# ledterne_driver.net
KiCad netlist of a schematic drawn in EAGLE
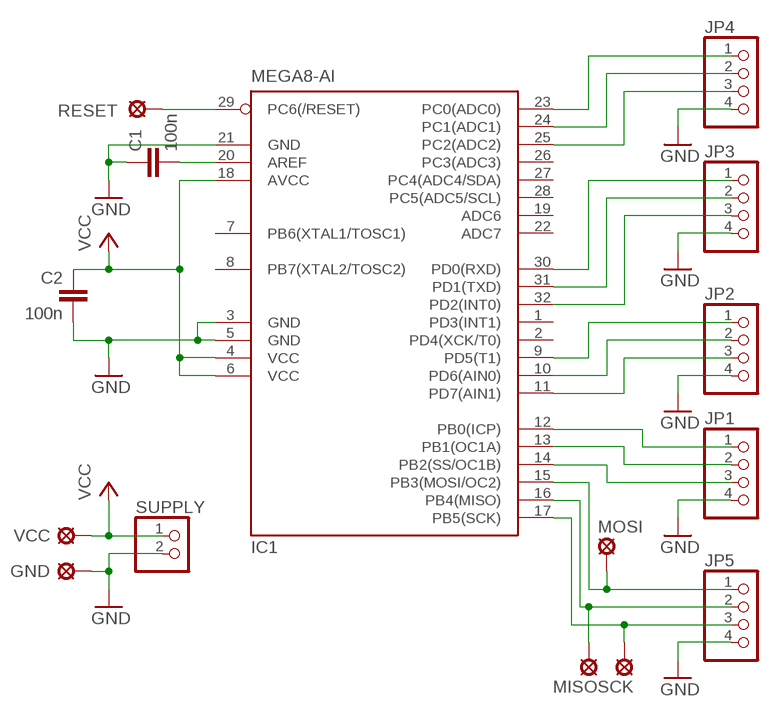
[diagram p0: schematic, sheet 1]

(export (version "E")
  (design (tool "Eeschema 10.0.6"))
  (components
    (comp (ref "C1")
      (value "100n")
      (footprint "eagle-import:C0805K")
      (libsource (lib "eagle-import") (part "C-EUC0805K"))
    )
    (comp (ref "C2")
      (value "100n")
      (footprint "eagle-import:C0805K")
      (libsource (lib "eagle-import") (part "C-EUC0805K"))
    )
    (comp (ref "GND")
      (value "LSP10")
      (footprint "eagle-import:LSP10")
      (libsource (lib "eagle-import") (part "LSP10"))
    )
    (comp (ref "IC1")
      (value "MEGA8-AI")
      (footprint "eagle-import:TQFP32-08")
      (fields (field (name "MPN") "ATMEGA8-16AU"))
      (libsource (lib "eagle-import") (part "MEGA8-AI"))
    )
    (comp (ref "JP1")
      (value "PINHD-1X4/90")
      (footprint "eagle-import:1X04_90")
      (libsource (lib "eagle-import") (part "PINHD-1X4/90"))
    )
    (comp (ref "JP2")
      (value "PINHD-1X4/90")
      (footprint "eagle-import:1X04_90")
      (libsource (lib "eagle-import") (part "PINHD-1X4/90"))
    )
    (comp (ref "JP3")
      (value "PINHD-1X4/90")
      (footprint "eagle-import:1X04_90")
      (libsource (lib "eagle-import") (part "PINHD-1X4/90"))
    )
    (comp (ref "JP4")
      (value "PINHD-1X4/90")
      (footprint "eagle-import:1X04_90")
      (libsource (lib "eagle-import") (part "PINHD-1X4/90"))
    )
    (comp (ref "JP5")
      (value "PINHD-1X4/90")
      (footprint "eagle-import:1X04_90")
      (libsource (lib "eagle-import") (part "PINHD-1X4/90"))
    )
    (comp (ref "MISO")
      (value "LSP10")
      (footprint "eagle-import:LSP10")
      (libsource (lib "eagle-import") (part "LSP10"))
    )
    (comp (ref "MOSI")
      (value "LSP10")
      (footprint "eagle-import:LSP10")
      (libsource (lib "eagle-import") (part "LSP10"))
    )
    (comp (ref "RESET")
      (value "LSP10")
      (footprint "eagle-import:LSP10")
      (libsource (lib "eagle-import") (part "LSP10"))
    )
    (comp (ref "SCK")
      (value "LSP10")
      (footprint "eagle-import:LSP10")
      (libsource (lib "eagle-import") (part "LSP10"))
    )
    (comp (ref "SUPPLY")
      (value "PINHD-1X2")
      (footprint "eagle-import:1X02")
      (libsource (lib "eagle-import") (part "PINHD-1X2"))
    )
    (comp (ref "VCC")
      (value "LSP10")
      (footprint "eagle-import:LSP10")
      (libsource (lib "eagle-import") (part "LSP10"))
    )
  )
  (nets
    (net (code "1") (name "GND") (class "Default")
      (node (ref "C1") (pin "1") (pinfunction "1_1") (pintype "passive"))
      (node (ref "C2") (pin "2") (pinfunction "2_2") (pintype "passive"))
      (node (ref "GND") (pin "MP") (pinfunction "MP_MP") (pintype "passive"))
      (node (ref "IC1") (pin "21") (pinfunction "GND_21") (pintype "power_in"))
      (node (ref "IC1") (pin "3") (pinfunction "GND_3") (pintype "power_in"))
      (node (ref "IC1") (pin "5") (pinfunction "GND_5") (pintype "power_in"))
      (node (ref "JP1") (pin "4") (pinfunction "4_4") (pintype "passive"))
      (node (ref "JP2") (pin "4") (pinfunction "4_4") (pintype "passive"))
      (node (ref "JP3") (pin "4") (pinfunction "4_4") (pintype "passive"))
      (node (ref "JP4") (pin "4") (pinfunction "4_4") (pintype "passive"))
      (node (ref "JP5") (pin "4") (pinfunction "4_4") (pintype "passive"))
      (node (ref "SUPPLY") (pin "2") (pinfunction "2_2") (pintype "passive"))
    )
    (net (code "2") (name "Net-(IC1-AREF)") (class "Default")
      (node (ref "C1") (pin "2") (pinfunction "2_2") (pintype "passive"))
      (node (ref "IC1") (pin "20") (pinfunction "AREF_20") (pintype "passive"))
    )
    (net (code "3") (name "Net-(IC1-PB0(ICP))") (class "Default")
      (node (ref "IC1") (pin "12") (pinfunction "PB0(ICP)_12") (pintype "bidirectional"))
      (node (ref "JP1") (pin "1") (pinfunction "1_1") (pintype "passive"))
    )
    (net (code "4") (name "Net-(IC1-PB1(OC1A))") (class "Default")
      (node (ref "IC1") (pin "13") (pinfunction "PB1(OC1A)_13") (pintype "bidirectional"))
      (node (ref "JP1") (pin "2") (pinfunction "2_2") (pintype "passive"))
    )
    (net (code "5") (name "Net-(IC1-PB2(SS{slash}OC1B))") (class "Default")
      (node (ref "IC1") (pin "14") (pinfunction "PB2(SS/OC1B)_14") (pintype "bidirectional"))
      (node (ref "JP1") (pin "3") (pinfunction "3_3") (pintype "passive"))
    )
    (net (code "6") (name "Net-(IC1-PB3(MOSI{slash}OC2))") (class "Default")
      (node (ref "IC1") (pin "15") (pinfunction "PB3(MOSI/OC2)_15") (pintype "bidirectional"))
      (node (ref "JP5") (pin "1") (pinfunction "1_1") (pintype "passive"))
      (node (ref "MOSI") (pin "MP") (pinfunction "MP_MP") (pintype "passive"))
    )
    (net (code "7") (name "Net-(IC1-PB4(MISO))") (class "Default")
      (node (ref "IC1") (pin "16") (pinfunction "PB4(MISO)_16") (pintype "bidirectional"))
      (node (ref "JP5") (pin "2") (pinfunction "2_2") (pintype "passive"))
      (node (ref "MISO") (pin "MP") (pinfunction "MP_MP") (pintype "passive"))
    )
    (net (code "8") (name "Net-(IC1-PB5(SCK))") (class "Default")
      (node (ref "IC1") (pin "17") (pinfunction "PB5(SCK)_17") (pintype "bidirectional"))
      (node (ref "JP5") (pin "3") (pinfunction "3_3") (pintype "passive"))
      (node (ref "SCK") (pin "MP") (pinfunction "MP_MP") (pintype "passive"))
    )
    (net (code "9") (name "Net-(IC1-PC0(ADC0))") (class "Default")
      (node (ref "IC1") (pin "23") (pinfunction "PC0(ADC0)_23") (pintype "bidirectional"))
      (node (ref "JP4") (pin "1") (pinfunction "1_1") (pintype "passive"))
    )
    (net (code "10") (name "Net-(IC1-PC1(ADC1))") (class "Default")
      (node (ref "IC1") (pin "24") (pinfunction "PC1(ADC1)_24") (pintype "bidirectional"))
      (node (ref "JP4") (pin "2") (pinfunction "2_2") (pintype "passive"))
    )
    (net (code "11") (name "Net-(IC1-PC2(ADC2))") (class "Default")
      (node (ref "IC1") (pin "25") (pinfunction "PC2(ADC2)_25") (pintype "bidirectional"))
      (node (ref "JP4") (pin "3") (pinfunction "3_3") (pintype "passive"))
    )
    (net (code "12") (name "Net-(IC1-PC6({slash}RESET))") (class "Default")
      (node (ref "IC1") (pin "29") (pinfunction "PC6(/RESET)_29") (pintype "bidirectional"))
      (node (ref "RESET") (pin "MP") (pinfunction "MP_MP") (pintype "passive"))
    )
    (net (code "13") (name "Net-(IC1-PD0(RXD))") (class "Default")
      (node (ref "IC1") (pin "30") (pinfunction "PD0(RXD)_30") (pintype "bidirectional"))
      (node (ref "JP3") (pin "1") (pinfunction "1_1") (pintype "passive"))
    )
    (net (code "14") (name "Net-(IC1-PD1(TXD))") (class "Default")
      (node (ref "IC1") (pin "31") (pinfunction "PD1(TXD)_31") (pintype "bidirectional"))
      (node (ref "JP3") (pin "2") (pinfunction "2_2") (pintype "passive"))
    )
    (net (code "15") (name "Net-(IC1-PD2(INT0))") (class "Default")
      (node (ref "IC1") (pin "32") (pinfunction "PD2(INT0)_32") (pintype "bidirectional"))
      (node (ref "JP3") (pin "3") (pinfunction "3_3") (pintype "passive"))
    )
    (net (code "16") (name "Net-(IC1-PD5(T1))") (class "Default")
      (node (ref "IC1") (pin "9") (pinfunction "PD5(T1)_9") (pintype "bidirectional"))
      (node (ref "JP2") (pin "1") (pinfunction "1_1") (pintype "passive"))
    )
    (net (code "17") (name "Net-(IC1-PD6(AIN0))") (class "Default")
      (node (ref "IC1") (pin "10") (pinfunction "PD6(AIN0)_10") (pintype "bidirectional"))
      (node (ref "JP2") (pin "2") (pinfunction "2_2") (pintype "passive"))
    )
    (net (code "18") (name "Net-(IC1-PD7(AIN1))") (class "Default")
      (node (ref "IC1") (pin "11") (pinfunction "PD7(AIN1)_11") (pintype "bidirectional"))
      (node (ref "JP2") (pin "3") (pinfunction "3_3") (pintype "passive"))
    )
    (net (code "19") (name "VCC") (class "Default")
      (node (ref "C2") (pin "1") (pinfunction "1_1") (pintype "passive"))
      (node (ref "IC1") (pin "18") (pinfunction "AVCC_18") (pintype "power_in"))
      (node (ref "IC1") (pin "4") (pinfunction "VCC_4") (pintype "power_in"))
      (node (ref "IC1") (pin "6") (pinfunction "VCC_6") (pintype "power_in"))
      (node (ref "SUPPLY") (pin "1") (pinfunction "1_1") (pintype "passive"))
      (node (ref "VCC") (pin "MP") (pinfunction "MP_MP") (pintype "passive"))
    )
    (net (code "20") (name "unconnected-(IC1-ADC6-Pad19)") (class "Default")
      (node (ref "IC1") (pin "19") (pinfunction "ADC6_19") (pintype "bidirectional"))
    )
    (net (code "21") (name "unconnected-(IC1-ADC7-Pad22)") (class "Default")
      (node (ref "IC1") (pin "22") (pinfunction "ADC7_22") (pintype "bidirectional"))
    )
    (net (code "22") (name "unconnected-(IC1-PB6(XTAL1{slash}TOSC1)-Pad7)") (class "Default")
      (node (ref "IC1") (pin "7") (pinfunction "PB6(XTAL1/TOSC1)_7") (pintype "bidirectional"))
    )
    (net (code "23") (name "unconnected-(IC1-PB7(XTAL2{slash}TOSC2)-Pad8)") (class "Default")
      (node (ref "IC1") (pin "8") (pinfunction "PB7(XTAL2/TOSC2)_8") (pintype "bidirectional"))
    )
    (net (code "24") (name "unconnected-(IC1-PC3(ADC3)-Pad26)") (class "Default")
      (node (ref "IC1") (pin "26") (pinfunction "PC3(ADC3)_26") (pintype "bidirectional"))
    )
    (net (code "25") (name "unconnected-(IC1-PC4(ADC4{slash}SDA)-Pad27)") (class "Default")
      (node (ref "IC1") (pin "27") (pinfunction "PC4(ADC4/SDA)_27") (pintype "bidirectional"))
    )
    (net (code "26") (name "unconnected-(IC1-PC5(ADC5{slash}SCL)-Pad28)") (class "Default")
      (node (ref "IC1") (pin "28") (pinfunction "PC5(ADC5/SCL)_28") (pintype "bidirectional"))
    )
    (net (code "27") (name "unconnected-(IC1-PD3(INT1)-Pad1)") (class "Default")
      (node (ref "IC1") (pin "1") (pinfunction "PD3(INT1)_1") (pintype "bidirectional"))
    )
    (net (code "28") (name "unconnected-(IC1-PD4(XCK{slash}T0)-Pad2)") (class "Default")
      (node (ref "IC1") (pin "2") (pinfunction "PD4(XCK/T0)_2") (pintype "bidirectional"))
    )
  )
)
